# Arduino_PID_for_Espresso_v2_Rev_C.net
KiCad netlist of a schematic drawn in EAGLE
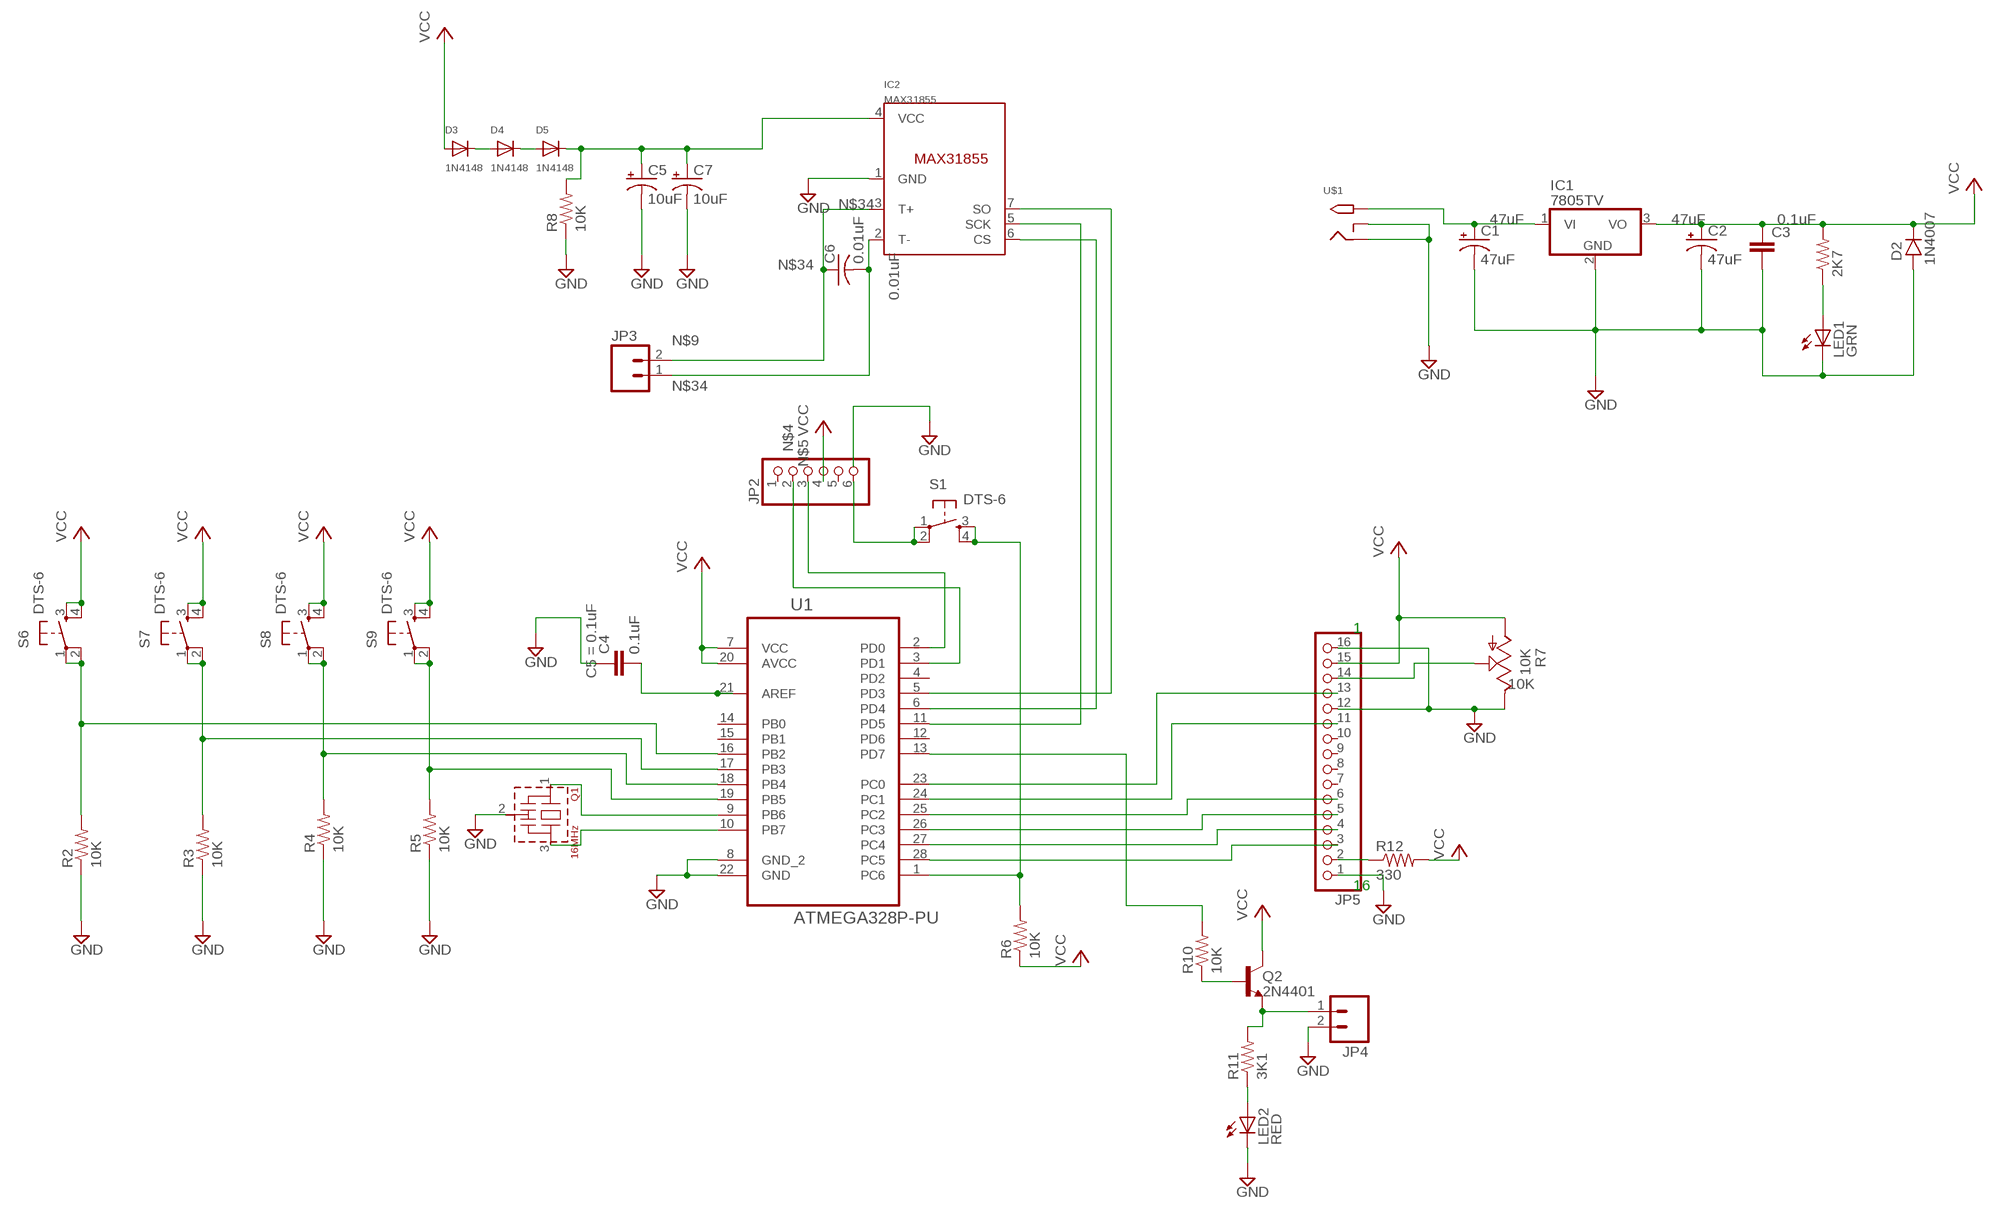
[diagram p0: schematic, sheet 1]

(export (version "E")
  (design (tool "Eeschema 10.0.6"))
  (components
    (comp (ref "C1")
      (value "47uF")
      (footprint "eagle-import:TT5D6")
      (fields (field (name "C1") "47uF"))
      (libsource (lib "eagle-import") (part "CPOL-USTT6D6"))
    )
    (comp (ref "C2")
      (value "47uF")
      (footprint "eagle-import:TT5D6")
      (fields (field (name "C2") "47uF"))
      (libsource (lib "eagle-import") (part "CPOL-USTT6D6"))
    )
    (comp (ref "C3")
      (value "C-EU025-024X044")
      (footprint "eagle-import:C025-024X044")
      (fields (field (name "C3") "0.1uF"))
      (libsource (lib "eagle-import") (part "C-EU025-024X044"))
    )
    (comp (ref "C4")
      (value "0.1uF")
      (footprint "eagle-import:C025-024X044")
      (fields (field (name "C5") "0.1uF"))
      (libsource (lib "eagle-import") (part "C-EU025-024X044"))
    )
    (comp (ref "C5")
      (value "10uF")
      (footprint "eagle-import:CPOL-RADIAL-10UF-25V")
      (libsource (lib "eagle-import") (part "CAP_POLPTH2"))
    )
    (comp (ref "C6")
      (value "0.01uF")
      (footprint "eagle-import:C025-024X044")
      (fields (field (name "C6") "0.01uF"))
      (libsource (lib "eagle-import") (part "C-US025-024X044"))
    )
    (comp (ref "C7")
      (value "10uF")
      (footprint "eagle-import:CPOL-RADIAL-10UF-25V")
      (libsource (lib "eagle-import") (part "CAP_POLPTH2"))
    )
    (comp (ref "D2")
      (value "1N4007")
      (footprint "eagle-import:DO41-3")
      (libsource (lib "eagle-import") (part "1N400X.3"))
    )
    (comp (ref "D3")
      (value "1N4148")
      (footprint "eagle-import:DO-1N4148")
      (libsource (lib "eagle-import") (part "DIODEDO-1N4148"))
    )
    (comp (ref "D4")
      (value "1N4148")
      (footprint "eagle-import:DO-1N4148")
      (libsource (lib "eagle-import") (part "DIODEDO-1N4148"))
    )
    (comp (ref "D5")
      (value "1N4148")
      (footprint "eagle-import:DO-1N4148")
      (libsource (lib "eagle-import") (part "DIODEDO-1N4148"))
    )
    (comp (ref "IC1")
      (value "7805TV")
      (footprint "eagle-import:TO220V")
      (libsource (lib "eagle-import") (part "78TV05"))
    )
    (comp (ref "IC2")
      (value "MAX31855")
      (footprint "eagle-import:SOIC8")
      (libsource (lib "eagle-import") (part "MAX31855"))
    )
    (comp (ref "JP2")
      (value "PINHD-1X6/90")
      (footprint "eagle-import:1X06_90")
      (libsource (lib "eagle-import") (part "PINHD-1X6/90"))
    )
    (comp (ref "JP3")
      (value "M023.5MM")
      (footprint "eagle-import:SCREWTERMINAL-3.5MM-2")
      (libsource (lib "eagle-import") (part "M023.5MM"))
    )
    (comp (ref "JP4")
      (value "M023.5MM")
      (footprint "eagle-import:SCREWTERMINAL-3.5MM-2")
      (libsource (lib "eagle-import") (part "M023.5MM"))
    )
    (comp (ref "JP5")
      (value "PINHD-1X16")
      (footprint "eagle-import:1X16")
      (libsource (lib "eagle-import") (part "PINHD-1X16"))
    )
    (comp (ref "LED1")
      (value "GRN")
      (footprint "eagle-import:LED3MM")
      (libsource (lib "eagle-import") (part "LED3MM"))
    )
    (comp (ref "LED2")
      (value "RED")
      (footprint "eagle-import:LED3MM")
      (libsource (lib "eagle-import") (part "LED3MM"))
    )
    (comp (ref "Q1")
      (value "16MHz")
      (footprint "eagle-import:CSTLA_T")
      (libsource (lib "eagle-import") (part "CSTLA_X"))
    )
    (comp (ref "Q2")
      (value "2N4401")
      (footprint "eagle-import:TO92-")
      (libsource (lib "eagle-import") (part "2N3904"))
    )
    (comp (ref "R1")
      (value "2K7")
      (footprint "eagle-import:AXIAL-0.4")
      (libsource (lib "eagle-import") (part "RESISTORPTH-1/4W"))
    )
    (comp (ref "R2")
      (value "10K")
      (footprint "eagle-import:1_6W-RES")
      (libsource (lib "eagle-import") (part "RESISTORPTH-1/6W"))
    )
    (comp (ref "R3")
      (value "10K")
      (footprint "eagle-import:1_6W-RES")
      (libsource (lib "eagle-import") (part "RESISTORPTH-1/6W"))
    )
    (comp (ref "R4")
      (value "10K")
      (footprint "eagle-import:1_6W-RES")
      (libsource (lib "eagle-import") (part "RESISTORPTH-1/6W"))
    )
    (comp (ref "R5")
      (value "10K")
      (footprint "eagle-import:1_6W-RES")
      (libsource (lib "eagle-import") (part "RESISTORPTH-1/6W"))
    )
    (comp (ref "R6")
      (value "10K")
      (footprint "eagle-import:1_6W-RES")
      (libsource (lib "eagle-import") (part "RESISTORPTH-1/6W"))
    )
    (comp (ref "R7")
      (value "10K")
      (footprint "eagle-import:B25P")
      (fields (field (name "VR1") "10K"))
      (libsource (lib "eagle-import") (part "TRIM_US-B25P"))
    )
    (comp (ref "R8")
      (value "10K")
      (footprint "eagle-import:1_6W-RES")
      (libsource (lib "eagle-import") (part "RESISTORPTH-1/6W"))
    )
    (comp (ref "R10")
      (value "10K")
      (footprint "eagle-import:1_6W-RES")
      (libsource (lib "eagle-import") (part "RESISTORPTH-1/6W"))
    )
    (comp (ref "R11")
      (value "3K1")
      (footprint "eagle-import:AXIAL-0.4")
      (libsource (lib "eagle-import") (part "SparkFun-Resistors_RESISTORPTH-1/4W"))
    )
    (comp (ref "R12")
      (value "330")
      (footprint "eagle-import:AXIAL-0.4")
      (libsource (lib "eagle-import") (part "RESISTORPTH-1/4W"))
    )
    (comp (ref "S1")
      (value "DTS-6")
      (footprint "eagle-import:DTS-6")
      (libsource (lib "eagle-import") (part "DTS-6"))
    )
    (comp (ref "S6")
      (value "DTS-6")
      (footprint "eagle-import:DTS-6")
      (libsource (lib "eagle-import") (part "DTS-6"))
    )
    (comp (ref "S7")
      (value "DTS-6")
      (footprint "eagle-import:DTS-6")
      (libsource (lib "eagle-import") (part "DTS-6"))
    )
    (comp (ref "S8")
      (value "DTS-6")
      (footprint "eagle-import:DTS-6")
      (libsource (lib "eagle-import") (part "DTS-6"))
    )
    (comp (ref "S9")
      (value "DTS-6")
      (footprint "eagle-import:DTS-6")
      (libsource (lib "eagle-import") (part "DTS-6"))
    )
    (comp (ref "U$1")
      (value "2.1MMJACKTHM")
      (footprint "eagle-import:PJ-102A")
      (libsource (lib "eagle-import") (part "2.1MMJACKTHM"))
    )
    (comp (ref "U1")
      (value "ATMEGA328P-PU")
      (footprint "eagle-import:DIP254P762X457-28")
      (libsource (lib "eagle-import") (part "ATMEGA328P-PU"))
    )
  )
  (nets
    (net (code "1") (name "/N$4") (class "Default")
      (node (ref "JP2") (pin "2") (pinfunction "2_2") (pintype "passive"))
      (node (ref "U1") (pin "3") (pinfunction "PD1_3") (pintype "bidirectional"))
    )
    (net (code "2") (name "/N$5") (class "Default")
      (node (ref "JP2") (pin "3") (pinfunction "3_3") (pintype "passive"))
      (node (ref "U1") (pin "2") (pinfunction "PD0_2") (pintype "bidirectional"))
    )
    (net (code "3") (name "/N$9") (class "Default")
      (node (ref "C6") (pin "2") (pinfunction "2_2") (pintype "passive"))
      (node (ref "IC2") (pin "2") (pinfunction "T-_2") (pintype "input"))
      (node (ref "JP3") (pin "1") (pinfunction "1_1") (pintype "passive"))
    )
    (net (code "4") (name "/N$34") (class "Default")
      (node (ref "C6") (pin "1") (pinfunction "1_1") (pintype "passive"))
      (node (ref "IC2") (pin "3") (pinfunction "T+_3") (pintype "input"))
      (node (ref "JP3") (pin "2") (pinfunction "2_2") (pintype "passive"))
    )
    (net (code "5") (name "GND") (class "Default")
      (node (ref "C1") (pin "-") (pinfunction "-_-") (pintype "passive"))
      (node (ref "C2") (pin "-") (pinfunction "-_-") (pintype "passive"))
      (node (ref "C3") (pin "2") (pinfunction "2_2") (pintype "passive"))
      (node (ref "C4") (pin "1") (pinfunction "1_1") (pintype "passive"))
      (node (ref "C5") (pin "2") (pinfunction "-_2") (pintype "passive"))
      (node (ref "C7") (pin "2") (pinfunction "-_2") (pintype "passive"))
      (node (ref "D2") (pin "A") (pinfunction "A_A") (pintype "passive"))
      (node (ref "IC1") (pin "2") (pinfunction "GND_2") (pintype "passive"))
      (node (ref "IC2") (pin "1") (pinfunction "GND_1") (pintype "power_in"))
      (node (ref "JP2") (pin "6") (pinfunction "6_6") (pintype "passive"))
      (node (ref "JP4") (pin "2") (pinfunction "2_2") (pintype "passive"))
      (node (ref "JP5") (pin "1") (pinfunction "1_1") (pintype "passive"))
      (node (ref "JP5") (pin "12") (pinfunction "12_12") (pintype "passive"))
      (node (ref "JP5") (pin "16") (pinfunction "16_16") (pintype "passive"))
      (node (ref "LED1") (pin "K") (pinfunction "C_K") (pintype "passive"))
      (node (ref "LED2") (pin "K") (pinfunction "C_K") (pintype "passive"))
      (node (ref "Q1") (pin "2") (pinfunction "VSS_2") (pintype "power_in"))
      (node (ref "R2") (pin "1") (pinfunction "1_1") (pintype "passive"))
      (node (ref "R3") (pin "1") (pinfunction "1_1") (pintype "passive"))
      (node (ref "R4") (pin "1") (pinfunction "1_1") (pintype "passive"))
      (node (ref "R5") (pin "1") (pinfunction "1_1") (pintype "passive"))
      (node (ref "R7") (pin "E") (pinfunction "E_E") (pintype "passive"))
      (node (ref "R8") (pin "1") (pinfunction "1_1") (pintype "passive"))
      (node (ref "S1") (pin "1") (pinfunction "1_1") (pintype "passive"))
      (node (ref "S1") (pin "2") (pinfunction "2_2") (pintype "passive"))
      (node (ref "U$1") (pin "RING") (pinfunction "RING_RING") (pintype "bidirectional"))
      (node (ref "U$1") (pin "RING_SW") (pinfunction "RING_SW_RING_SW") (pintype "bidirectional"))
      (node (ref "U1") (pin "22") (pinfunction "GND_22") (pintype "passive"))
      (node (ref "U1") (pin "8") (pinfunction "GND_2_8") (pintype "passive"))
    )
    (net (code "6") (name "Net-(C5-+)") (class "Default")
      (node (ref "C5") (pin "1") (pinfunction "+_1") (pintype "passive"))
      (node (ref "C7") (pin "1") (pinfunction "+_1") (pintype "passive"))
      (node (ref "D5") (pin "C") (pinfunction "C_C") (pintype "passive"))
      (node (ref "IC2") (pin "4") (pinfunction "VCC_4") (pintype "power_in"))
      (node (ref "R8") (pin "2") (pinfunction "2_2") (pintype "passive"))
    )
    (net (code "7") (name "Net-(D3-PadC)") (class "Default")
      (node (ref "D3") (pin "C") (pinfunction "C_C") (pintype "passive"))
      (node (ref "D4") (pin "A") (pinfunction "A_A") (pintype "passive"))
    )
    (net (code "8") (name "Net-(D4-PadC)") (class "Default")
      (node (ref "D4") (pin "C") (pinfunction "C_C") (pintype "passive"))
      (node (ref "D5") (pin "A") (pinfunction "A_A") (pintype "passive"))
    )
    (net (code "9") (name "Net-(IC1-VI)") (class "Default")
      (node (ref "C1") (pin "+") (pinfunction "+_+") (pintype "passive"))
      (node (ref "IC1") (pin "1") (pinfunction "VI_1") (pintype "input"))
      (node (ref "U$1") (pin "TIP") (pinfunction "TIP_TIP") (pintype "bidirectional"))
    )
    (net (code "10") (name "Net-(IC2-CS)") (class "Default")
      (node (ref "IC2") (pin "6") (pinfunction "CS_6") (pintype "input"))
      (node (ref "U1") (pin "6") (pinfunction "PD4_6") (pintype "bidirectional"))
    )
    (net (code "11") (name "Net-(IC2-SCK)") (class "Default")
      (node (ref "IC2") (pin "5") (pinfunction "SCK_5") (pintype "input"))
      (node (ref "U1") (pin "11") (pinfunction "PD5_11") (pintype "bidirectional"))
    )
    (net (code "12") (name "Net-(IC2-SO)") (class "Default")
      (node (ref "IC2") (pin "7") (pinfunction "SO_7") (pintype "output"))
      (node (ref "U1") (pin "5") (pinfunction "PD3_5") (pintype "bidirectional"))
    )
    (net (code "13") (name "Net-(JP5-Pad14)") (class "Default")
      (node (ref "JP5") (pin "14") (pinfunction "14_14") (pintype "passive"))
      (node (ref "R7") (pin "S") (pinfunction "S_S") (pintype "passive"))
    )
    (net (code "14") (name "Net-(Q2-B)") (class "Default")
      (node (ref "Q2") (pin "2") (pinfunction "B_2") (pintype "passive"))
      (node (ref "R10") (pin "1") (pinfunction "1_1") (pintype "passive"))
    )
    (net (code "15") (name "Net-(Q2-E)") (class "Default")
      (node (ref "JP4") (pin "1") (pinfunction "1_1") (pintype "passive"))
      (node (ref "Q2") (pin "3") (pinfunction "E_3") (pintype "passive"))
      (node (ref "R11") (pin "P$2") (pinfunction "2_P$2") (pintype "passive"))
    )
    (net (code "16") (name "Net-(R1-1)") (class "Default")
      (node (ref "LED1") (pin "A") (pinfunction "A_A") (pintype "passive"))
      (node (ref "R1") (pin "P$1") (pinfunction "1_P$1") (pintype "passive"))
    )
    (net (code "17") (name "Net-(R11-1)") (class "Default")
      (node (ref "LED2") (pin "A") (pinfunction "A_A") (pintype "passive"))
      (node (ref "R11") (pin "P$1") (pinfunction "1_P$1") (pintype "passive"))
    )
    (net (code "18") (name "Net-(R12-1)") (class "Default")
      (node (ref "JP5") (pin "2") (pinfunction "2_2") (pintype "passive"))
      (node (ref "R12") (pin "P$1") (pinfunction "1_P$1") (pintype "passive"))
    )
    (net (code "19") (name "Net-(U1-AREF)") (class "Default")
      (node (ref "C4") (pin "2") (pinfunction "2_2") (pintype "passive"))
      (node (ref "U1") (pin "21") (pinfunction "AREF_21") (pintype "input"))
    )
    (net (code "20") (name "Net-(U1-PB2)") (class "Default")
      (node (ref "R2") (pin "2") (pinfunction "2_2") (pintype "passive"))
      (node (ref "S6") (pin "1") (pinfunction "1_1") (pintype "passive"))
      (node (ref "S6") (pin "2") (pinfunction "2_2") (pintype "passive"))
      (node (ref "U1") (pin "16") (pinfunction "PB2_16") (pintype "bidirectional"))
    )
    (net (code "21") (name "Net-(U1-PB3)") (class "Default")
      (node (ref "R3") (pin "2") (pinfunction "2_2") (pintype "passive"))
      (node (ref "S7") (pin "1") (pinfunction "1_1") (pintype "passive"))
      (node (ref "S7") (pin "2") (pinfunction "2_2") (pintype "passive"))
      (node (ref "U1") (pin "17") (pinfunction "PB3_17") (pintype "bidirectional"))
    )
    (net (code "22") (name "Net-(U1-PB4)") (class "Default")
      (node (ref "R4") (pin "2") (pinfunction "2_2") (pintype "passive"))
      (node (ref "S8") (pin "1") (pinfunction "1_1") (pintype "passive"))
      (node (ref "S8") (pin "2") (pinfunction "2_2") (pintype "passive"))
      (node (ref "U1") (pin "18") (pinfunction "PB4_18") (pintype "bidirectional"))
    )
    (net (code "23") (name "Net-(U1-PB5)") (class "Default")
      (node (ref "R5") (pin "2") (pinfunction "2_2") (pintype "passive"))
      (node (ref "S9") (pin "1") (pinfunction "1_1") (pintype "passive"))
      (node (ref "S9") (pin "2") (pinfunction "2_2") (pintype "passive"))
      (node (ref "U1") (pin "19") (pinfunction "PB5_19") (pintype "bidirectional"))
    )
    (net (code "24") (name "Net-(U1-PB6)") (class "Default")
      (node (ref "Q1") (pin "1") (pinfunction "1_1") (pintype "output"))
      (node (ref "U1") (pin "9") (pinfunction "PB6_9") (pintype "bidirectional"))
    )
    (net (code "25") (name "Net-(U1-PB7)") (class "Default")
      (node (ref "Q1") (pin "3") (pinfunction "3_3") (pintype "input"))
      (node (ref "U1") (pin "10") (pinfunction "PB7_10") (pintype "bidirectional"))
    )
    (net (code "26") (name "Net-(U1-PC0)") (class "Default")
      (node (ref "JP5") (pin "13") (pinfunction "13_13") (pintype "passive"))
      (node (ref "U1") (pin "23") (pinfunction "PC0_23") (pintype "bidirectional"))
    )
    (net (code "27") (name "Net-(U1-PC1)") (class "Default")
      (node (ref "JP5") (pin "11") (pinfunction "11_11") (pintype "passive"))
      (node (ref "U1") (pin "24") (pinfunction "PC1_24") (pintype "bidirectional"))
    )
    (net (code "28") (name "Net-(U1-PC2)") (class "Default")
      (node (ref "JP5") (pin "6") (pinfunction "6_6") (pintype "passive"))
      (node (ref "U1") (pin "25") (pinfunction "PC2_25") (pintype "bidirectional"))
    )
    (net (code "29") (name "Net-(U1-PC3)") (class "Default")
      (node (ref "JP5") (pin "5") (pinfunction "5_5") (pintype "passive"))
      (node (ref "U1") (pin "26") (pinfunction "PC3_26") (pintype "bidirectional"))
    )
    (net (code "30") (name "Net-(U1-PC4)") (class "Default")
      (node (ref "JP5") (pin "4") (pinfunction "4_4") (pintype "passive"))
      (node (ref "U1") (pin "27") (pinfunction "PC4_27") (pintype "bidirectional"))
    )
    (net (code "31") (name "Net-(U1-PC5)") (class "Default")
      (node (ref "JP5") (pin "3") (pinfunction "3_3") (pintype "passive"))
      (node (ref "U1") (pin "28") (pinfunction "PC5_28") (pintype "bidirectional"))
    )
    (net (code "32") (name "Net-(U1-PC6)") (class "Default")
      (node (ref "R6") (pin "2") (pinfunction "2_2") (pintype "passive"))
      (node (ref "S1") (pin "3") (pinfunction "3_3") (pintype "passive"))
      (node (ref "S1") (pin "4") (pinfunction "4_4") (pintype "passive"))
      (node (ref "U1") (pin "1") (pinfunction "PC6_1") (pintype "bidirectional"))
    )
    (net (code "33") (name "Net-(U1-PD7)") (class "Default")
      (node (ref "R10") (pin "2") (pinfunction "2_2") (pintype "passive"))
      (node (ref "U1") (pin "13") (pinfunction "PD7_13") (pintype "bidirectional"))
    )
    (net (code "34") (name "VCC") (class "Default")
      (node (ref "C2") (pin "+") (pinfunction "+_+") (pintype "passive"))
      (node (ref "C3") (pin "1") (pinfunction "1_1") (pintype "passive"))
      (node (ref "D2") (pin "C") (pinfunction "C_C") (pintype "passive"))
      (node (ref "D3") (pin "A") (pinfunction "A_A") (pintype "passive"))
      (node (ref "IC1") (pin "3") (pinfunction "VO_3") (pintype "passive"))
      (node (ref "JP2") (pin "4") (pinfunction "4_4") (pintype "passive"))
      (node (ref "JP5") (pin "15") (pinfunction "15_15") (pintype "passive"))
      (node (ref "Q2") (pin "1") (pinfunction "C_1") (pintype "passive"))
      (node (ref "R1") (pin "P$2") (pinfunction "2_P$2") (pintype "passive"))
      (node (ref "R12") (pin "P$2") (pinfunction "2_P$2") (pintype "passive"))
      (node (ref "R6") (pin "1") (pinfunction "1_1") (pintype "passive"))
      (node (ref "R7") (pin "A") (pinfunction "A_A") (pintype "passive"))
      (node (ref "S6") (pin "3") (pinfunction "3_3") (pintype "passive"))
      (node (ref "S6") (pin "4") (pinfunction "4_4") (pintype "passive"))
      (node (ref "S7") (pin "3") (pinfunction "3_3") (pintype "passive"))
      (node (ref "S7") (pin "4") (pinfunction "4_4") (pintype "passive"))
      (node (ref "S8") (pin "3") (pinfunction "3_3") (pintype "passive"))
      (node (ref "S8") (pin "4") (pinfunction "4_4") (pintype "passive"))
      (node (ref "S9") (pin "3") (pinfunction "3_3") (pintype "passive"))
      (node (ref "S9") (pin "4") (pinfunction "4_4") (pintype "passive"))
      (node (ref "U1") (pin "20") (pinfunction "AVCC_20") (pintype "power_in"))
      (node (ref "U1") (pin "7") (pinfunction "VCC_7") (pintype "power_in"))
    )
    (net (code "35") (name "unconnected-(JP2-Pad1)") (class "Default")
      (node (ref "JP2") (pin "1") (pinfunction "1_1") (pintype "passive"))
    )
    (net (code "36") (name "unconnected-(JP2-Pad5)") (class "Default")
      (node (ref "JP2") (pin "5") (pinfunction "5_5") (pintype "passive"))
    )
    (net (code "37") (name "unconnected-(JP5-Pad7)") (class "Default")
      (node (ref "JP5") (pin "7") (pinfunction "7_7") (pintype "passive"))
    )
    (net (code "38") (name "unconnected-(JP5-Pad8)") (class "Default")
      (node (ref "JP5") (pin "8") (pinfunction "8_8") (pintype "passive"))
    )
    (net (code "39") (name "unconnected-(JP5-Pad9)") (class "Default")
      (node (ref "JP5") (pin "9") (pinfunction "9_9") (pintype "passive"))
    )
    (net (code "40") (name "unconnected-(JP5-Pad10)") (class "Default")
      (node (ref "JP5") (pin "10") (pinfunction "10_10") (pintype "passive"))
    )
    (net (code "41") (name "unconnected-(U1-PB0-Pad14)") (class "Default")
      (node (ref "U1") (pin "14") (pinfunction "PB0_14") (pintype "bidirectional"))
    )
    (net (code "42") (name "unconnected-(U1-PB1-Pad15)") (class "Default")
      (node (ref "U1") (pin "15") (pinfunction "PB1_15") (pintype "bidirectional"))
    )
    (net (code "43") (name "unconnected-(U1-PD2-Pad4)") (class "Default")
      (node (ref "U1") (pin "4") (pinfunction "PD2_4") (pintype "bidirectional"))
    )
    (net (code "44") (name "unconnected-(U1-PD6-Pad12)") (class "Default")
      (node (ref "U1") (pin "12") (pinfunction "PD6_12") (pintype "bidirectional"))
    )
  )
)
